# UWB_Fuente-Cargador.net
KiCad netlist of a schematic drawn in Altium Designer
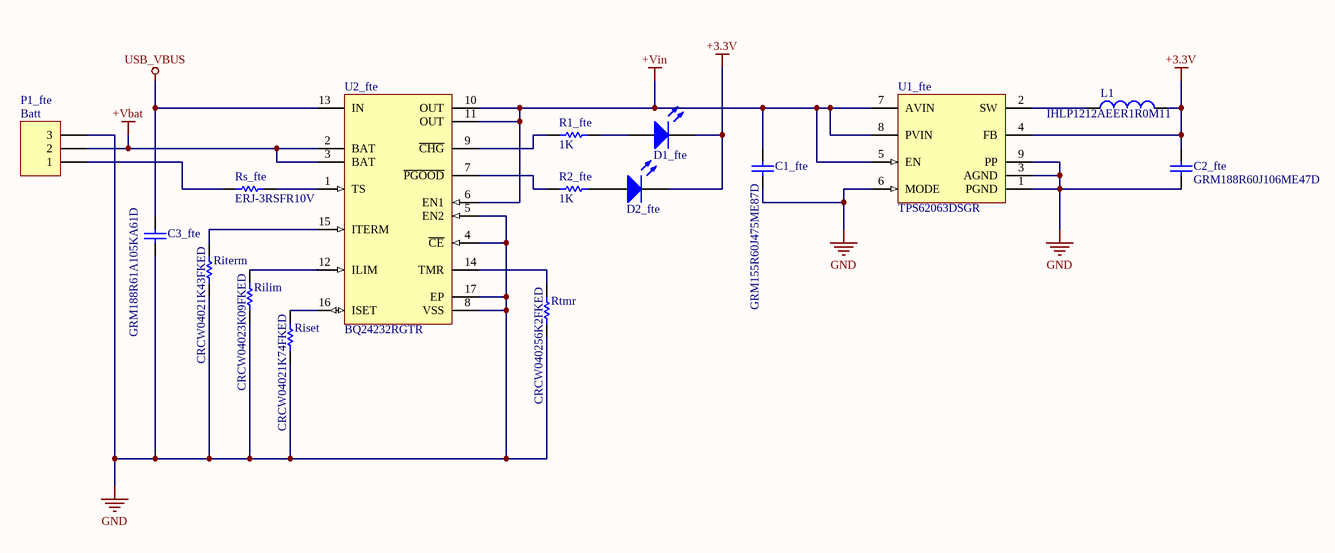
[diagram p0: UWB_Fuente-Cargador.SchDoc]

(export (version "E")
  (design (tool "Eeschema 10.0.6"))
  (components
    (comp (ref "C1_fte")
      (value "GRM155R60J475ME87D")
      (footprint "CAPC1005N")
      (description "Capacitor")
      (fields (field (name "Comment") "Cap") (field (name "PUBLISHER") "Altium Limited"))
      (libsource (lib "Leo") (part "Cap"))
    )
    (comp (ref "C2_fte")
      (value "GRM188R60J106ME47D")
      (footprint "CAPC1608N")
      (description "Capacitor")
      (fields (field (name "Comment") "Cap") (field (name "PUBLISHER") "Altium Limited"))
      (libsource (lib "Leo") (part "Cap"))
    )
    (comp (ref "C3_fte")
      (value "GRM188R61A105KA61D")
      (footprint "CAPC1608N")
      (description "Capacitor")
      (fields (field (name "Comment") "Cap") (field (name "PUBLISHER") "Altium Limited"))
      (libsource (lib "Leo") (part "Cap"))
    )
    (comp (ref "D1_fte")
      (value "LED")
      (footprint "LED SMD 0805")
      (description "Typical INFRARED GaAs LED")
      (fields (field (name "PUBLISHER") "Altium Limited"))
      (libsource (lib "Leo") (part "LED"))
    )
    (comp (ref "D2_fte")
      (value "LED")
      (footprint "LED SMD 0805")
      (description "Typical INFRARED GaAs LED")
      (fields (field (name "PUBLISHER") "Altium Limited"))
      (libsource (lib "Leo") (part "LED"))
    )
    (comp (ref "L1")
      (value "IHLP1212AEER1R0M11")
      (footprint "IHLP-1212AE")
      (description "Inductor")
      (fields (field (name "PUBLISHER") "Altium Limited"))
      (libsource (lib "Leo") (part "Inductor"))
    )
    (comp (ref "P1_fte")
      (value "Batt")
      (footprint "HDR1X3")
      (description "Header, 3-Pin MCU")
      (fields (field (name "PUBLISHER") "Altium Limited"))
      (libsource (lib "Leo") (part "Header 3"))
    )
    (comp (ref "R1_fte")
      (value "1K")
      (footprint "RESC1608N")
      (description "Resistor")
      (fields (field (name "Comment") "Res1") (field (name "PUBLISHER") "Altium Limited"))
      (libsource (lib "Leo") (part "Res1"))
    )
    (comp (ref "R2_fte")
      (value "1K")
      (footprint "RESC1608N")
      (description "Resistor")
      (fields (field (name "Comment") "Res1") (field (name "PUBLISHER") "Altium Limited"))
      (libsource (lib "Leo") (part "Res1"))
    )
    (comp (ref "Rilim")
      (value "CRCW04023K09FKED")
      (footprint "RESC1005N")
      (description "Resistor")
      (fields (field (name "Comment") "Res1") (field (name "PUBLISHER") "Altium Limited"))
      (libsource (lib "Leo") (part "Res1"))
    )
    (comp (ref "Riset")
      (value "CRCW04021K74FKED")
      (footprint "RESC1005N")
      (description "Resistor")
      (fields (field (name "Comment") "Res1") (field (name "PUBLISHER") "Altium Limited"))
      (libsource (lib "Leo") (part "Res1"))
    )
    (comp (ref "Riterm")
      (value "CRCW04021K43FKED")
      (footprint "RESC1005N")
      (description "Resistor")
      (fields (field (name "Comment") "Res1") (field (name "PUBLISHER") "Altium Limited"))
      (libsource (lib "Leo") (part "Res1"))
    )
    (comp (ref "Rs_fte")
      (value "ERJ-3RSFR10V")
      (footprint "RESC1608N")
      (description "Resistor")
      (fields (field (name "Comment") "Res1") (field (name "PUBLISHER") "Altium Limited"))
      (libsource (lib "Leo") (part "Res1"))
    )
    (comp (ref "Rtmr")
      (value "CRCW040256K2FKED")
      (footprint "RESC1005N")
      (description "Resistor")
      (fields (field (name "Comment") "Res1") (field (name "PUBLISHER") "Altium Limited"))
      (libsource (lib "Leo") (part "Res1"))
    )
    (comp (ref "U1_fte")
      (value "TPS62063DSGR")
      (footprint "DSG8-1600X900TP")
      (fields (field (name "MANUFACTURER") "Texas Instruments"))
      (libsource (lib "TI Power Management Step-Down Regulator") (part "TPS62063DSGR"))
    )
    (comp (ref "U2_fte")
      (value "BQ24232RGTR")
      (footprint "RGT16-1700X1700TP")
      (fields (field (name "MANUFACTURER") "Texas Instruments"))
      (libsource (lib "TI Power Management Battery Management") (part "BQ24232RGTR"))
    )
  )
  (nets
    (net (code "1") (name "+3.3V") (class "Default")
      (node (ref "C2_fte") (pin "1") (pinfunction "1_1") (pintype "passive"))
      (node (ref "D1_fte") (pin "K") (pinfunction "K_K") (pintype "passive"))
      (node (ref "D2_fte") (pin "K") (pinfunction "K_K") (pintype "passive"))
      (node (ref "L1") (pin "1") (pinfunction "1_1") (pintype "passive"))
      (node (ref "U1_fte") (pin "4") (pinfunction "FB_4") (pintype "passive"))
    )
    (net (code "2") (name "+Vbat") (class "Default")
      (node (ref "P1_fte") (pin "2") (pinfunction "2_2") (pintype "passive"))
      (node (ref "U2_fte") (pin "2") (pinfunction "BAT_2") (pintype "power_in"))
      (node (ref "U2_fte") (pin "3") (pinfunction "BAT_3") (pintype "power_in"))
    )
    (net (code "3") (name "+Vin") (class "Default")
      (node (ref "C1_fte") (pin "1") (pinfunction "1_1") (pintype "passive"))
      (node (ref "U1_fte") (pin "5") (pinfunction "EN_5") (pintype "input"))
      (node (ref "U1_fte") (pin "7") (pinfunction "AVIN_7") (pintype "power_in"))
      (node (ref "U1_fte") (pin "8") (pinfunction "PVIN_8") (pintype "power_in"))
      (node (ref "U2_fte") (pin "10") (pinfunction "OUT_10") (pintype "power_in"))
      (node (ref "U2_fte") (pin "11") (pinfunction "OUT_11") (pintype "power_in"))
      (node (ref "U2_fte") (pin "6") (pinfunction "EN1_6") (pintype "input"))
    )
    (net (code "4") (name "GND") (class "Default")
      (node (ref "C1_fte") (pin "2") (pinfunction "2_2") (pintype "passive"))
      (node (ref "C2_fte") (pin "2") (pinfunction "2_2") (pintype "passive"))
      (node (ref "C3_fte") (pin "2") (pinfunction "2_2") (pintype "passive"))
      (node (ref "P1_fte") (pin "3") (pinfunction "3_3") (pintype "passive"))
      (node (ref "Rilim") (pin "1") (pinfunction "1_1") (pintype "passive"))
      (node (ref "Riset") (pin "1") (pinfunction "1_1") (pintype "passive"))
      (node (ref "Riterm") (pin "1") (pinfunction "1_1") (pintype "passive"))
      (node (ref "Rtmr") (pin "1") (pinfunction "1_1") (pintype "passive"))
      (node (ref "U1_fte") (pin "1") (pinfunction "PGND_1") (pintype "power_in"))
      (node (ref "U1_fte") (pin "3") (pinfunction "AGND_3") (pintype "power_in"))
      (node (ref "U1_fte") (pin "6") (pinfunction "MODE_6") (pintype "input"))
      (node (ref "U1_fte") (pin "9") (pinfunction "PP_9") (pintype "power_in"))
      (node (ref "U2_fte") (pin "17") (pinfunction "EP_17") (pintype "power_in"))
      (node (ref "U2_fte") (pin "4") (pinfunction "~{CE}_4") (pintype "input"))
      (node (ref "U2_fte") (pin "5") (pinfunction "EN2_5") (pintype "input"))
      (node (ref "U2_fte") (pin "8") (pinfunction "VSS_8") (pintype "power_in"))
    )
    (net (code "5") (name "Net-(D1_fte-PadA)") (class "Default")
      (node (ref "D1_fte") (pin "A") (pinfunction "A_A") (pintype "passive"))
      (node (ref "R1_fte") (pin "2") (pinfunction "2_2") (pintype "passive"))
    )
    (net (code "6") (name "Net-(D2_fte-PadA)") (class "Default")
      (node (ref "D2_fte") (pin "A") (pinfunction "A_A") (pintype "passive"))
      (node (ref "R2_fte") (pin "2") (pinfunction "2_2") (pintype "passive"))
    )
    (net (code "7") (name "Net-(P1_fte-Pad1)") (class "Default")
      (node (ref "P1_fte") (pin "1") (pinfunction "1_1") (pintype "passive"))
      (node (ref "Rs_fte") (pin "1") (pinfunction "1_1") (pintype "passive"))
    )
    (net (code "8") (name "Net-(U1_fte-SW)") (class "Default")
      (node (ref "L1") (pin "2") (pinfunction "2_2") (pintype "passive"))
      (node (ref "U1_fte") (pin "2") (pinfunction "SW_2") (pintype "power_in"))
    )
    (net (code "9") (name "Net-(U2_fte-ILIM)") (class "Default")
      (node (ref "Rilim") (pin "2") (pinfunction "2_2") (pintype "passive"))
      (node (ref "U2_fte") (pin "12") (pinfunction "ILIM_12") (pintype "input"))
    )
    (net (code "10") (name "Net-(U2_fte-ISET)") (class "Default")
      (node (ref "Riset") (pin "2") (pinfunction "2_2") (pintype "passive"))
      (node (ref "U2_fte") (pin "16") (pinfunction "ISET_16") (pintype "bidirectional"))
    )
    (net (code "11") (name "Net-(U2_fte-ITERM)") (class "Default")
      (node (ref "Riterm") (pin "2") (pinfunction "2_2") (pintype "passive"))
      (node (ref "U2_fte") (pin "15") (pinfunction "ITERM_15") (pintype "input"))
    )
    (net (code "12") (name "Net-(U2_fte-TMR)") (class "Default")
      (node (ref "Rtmr") (pin "2") (pinfunction "2_2") (pintype "passive"))
      (node (ref "U2_fte") (pin "14") (pinfunction "TMR_14") (pintype "passive"))
    )
    (net (code "13") (name "Net-(U2_fte-TS)") (class "Default")
      (node (ref "Rs_fte") (pin "2") (pinfunction "2_2") (pintype "passive"))
      (node (ref "U2_fte") (pin "1") (pinfunction "TS_1") (pintype "input"))
    )
    (net (code "14") (name "Net-(U2_fte-~{CHG})") (class "Default")
      (node (ref "R1_fte") (pin "1") (pinfunction "1_1") (pintype "passive"))
      (node (ref "U2_fte") (pin "9") (pinfunction "~{CHG}_9") (pintype "tri_state"))
    )
    (net (code "15") (name "Net-(U2_fte-~{PGOOD})") (class "Default")
      (node (ref "R2_fte") (pin "1") (pinfunction "1_1") (pintype "passive"))
      (node (ref "U2_fte") (pin "7") (pinfunction "~{PGOOD}_7") (pintype "tri_state"))
    )
    (net (code "16") (name "USB_VBUS") (class "Default")
      (node (ref "C3_fte") (pin "1") (pinfunction "1_1") (pintype "passive"))
      (node (ref "U2_fte") (pin "13") (pinfunction "IN_13") (pintype "power_in"))
    )
  )
)
